# battery_box3.net
KiCad netlist of a schematic drawn in EAGLE
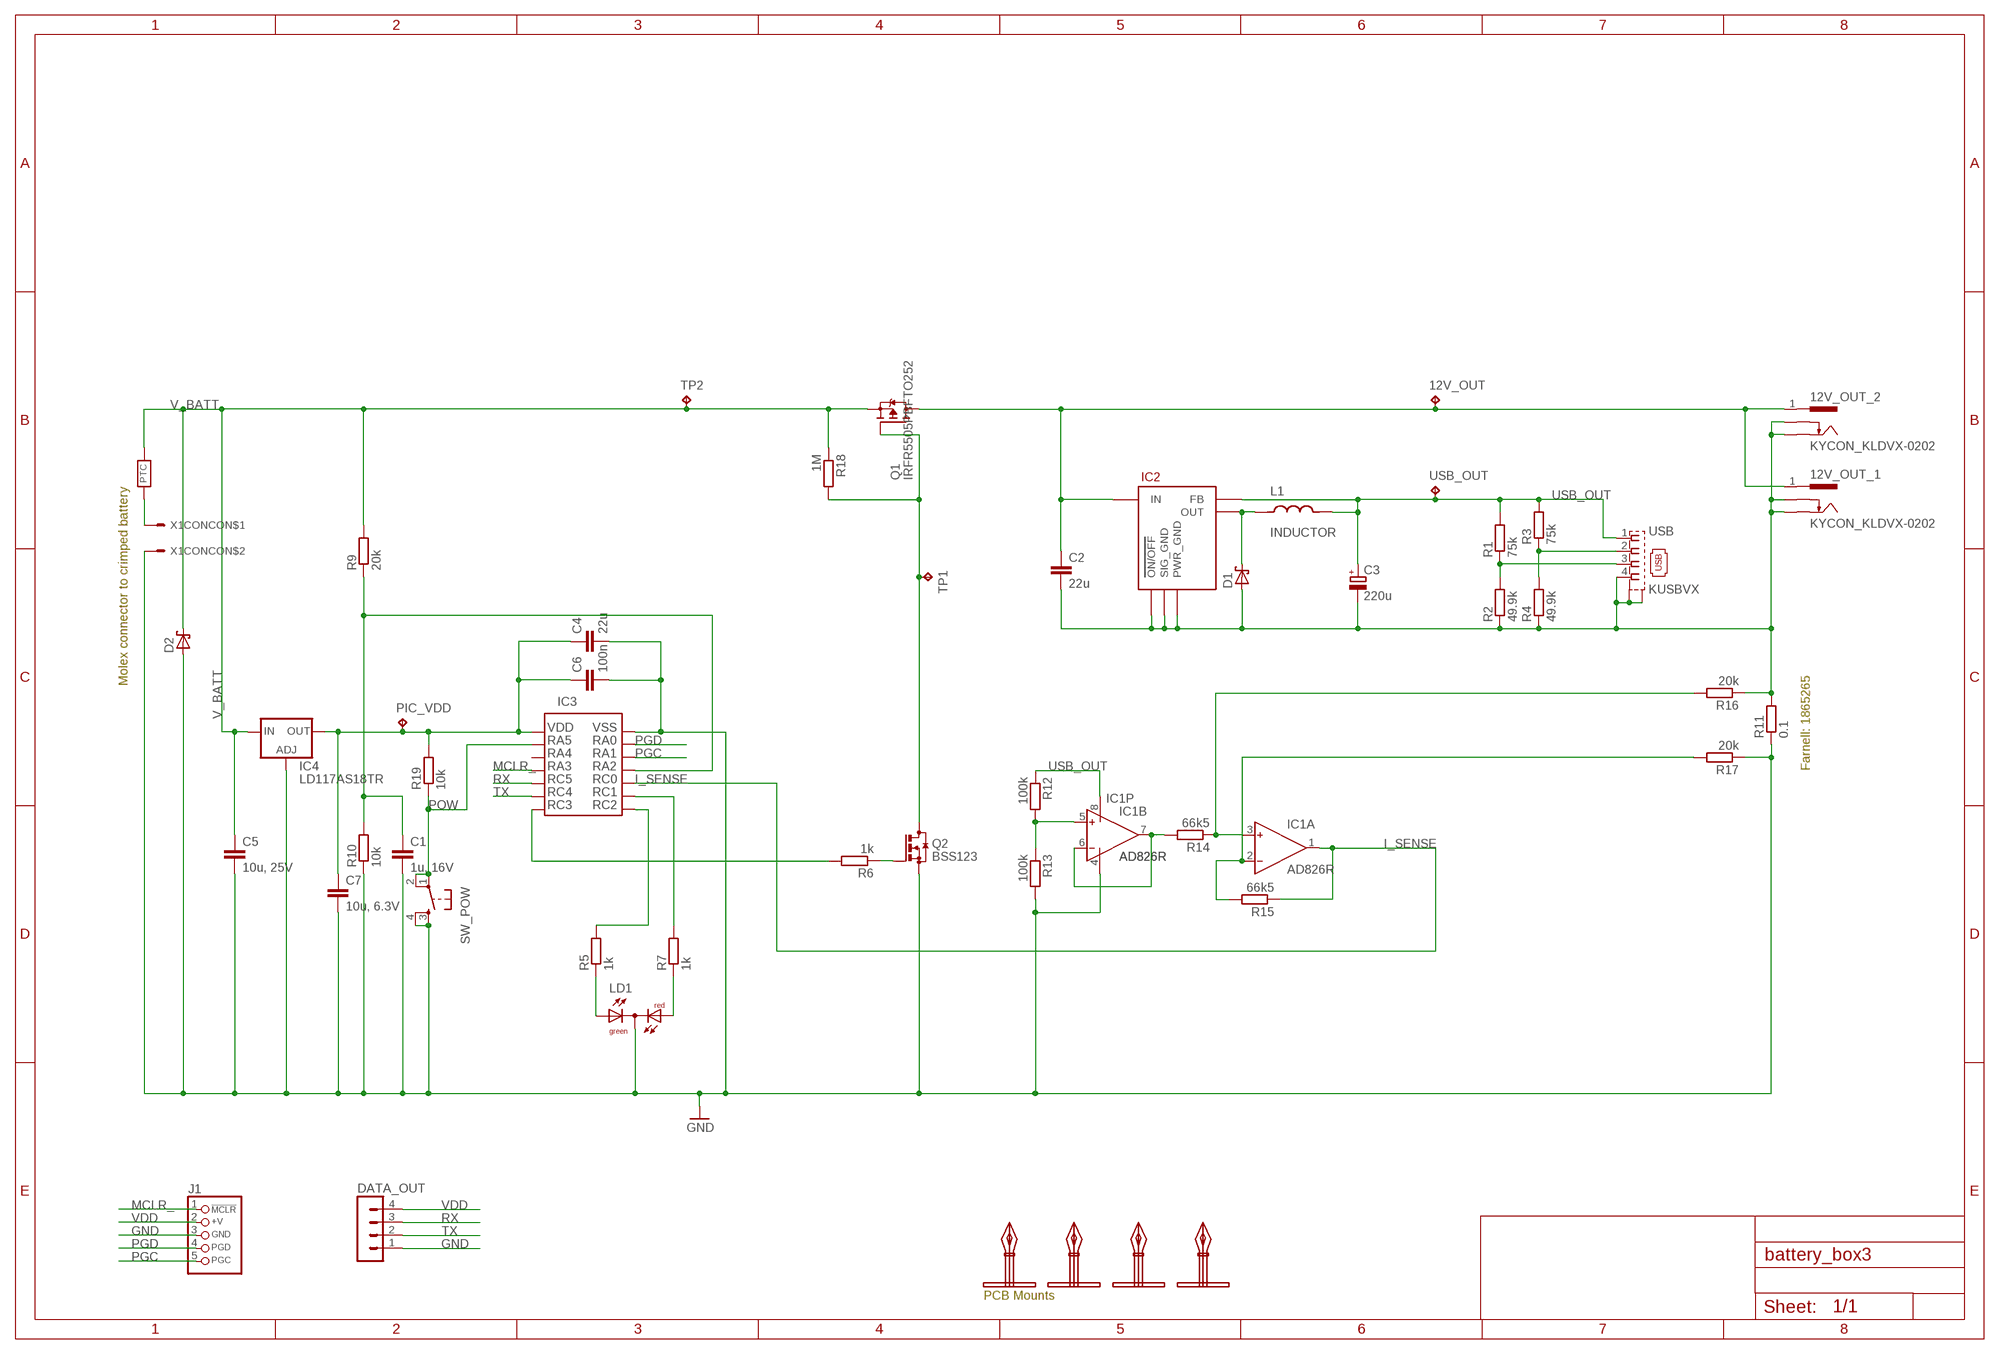
[diagram p0: schematic, sheet 1]

(export (version "E")
  (design (tool "Eeschema 10.0.6"))
  (components
    (comp (ref "12V_OUT")
      (value "TPTP20R")
      (footprint "eagle-import:TP20R")
      (libsource (lib "eagle-import") (part "TPTP20R"))
    )
    (comp (ref "12V_OUT_1")
      (value "KYCON_KLDVX-0202")
      (footprint "eagle-import:KYCON_KLVDX_2020_B")
      (libsource (lib "eagle-import") (part "KYCON_KLDVX-0202"))
    )
    (comp (ref "12V_OUT_2")
      (value "KYCON_KLDVX-0202")
      (footprint "eagle-import:KYCON_KLVDX_2020_B")
      (libsource (lib "eagle-import") (part "KYCON_KLDVX-0202"))
    )
    (comp (ref "C1")
      (value "1u, 16V")
      (footprint "eagle-import:C0805")
      (libsource (lib "eagle-import") (part "C-EUC0805"))
    )
    (comp (ref "C2")
      (value "22u")
      (footprint "eagle-import:C1210")
      (libsource (lib "eagle-import") (part "C-EUC1210"))
    )
    (comp (ref "C3")
      (value "220u")
      (footprint "eagle-import:PANASONIC_E")
      (libsource (lib "eagle-import") (part "CPOL-EUE"))
    )
    (comp (ref "C4")
      (value "22u")
      (footprint "eagle-import:C0805")
      (libsource (lib "eagle-import") (part "C-EUC0805"))
    )
    (comp (ref "C5")
      (value "10u, 25V")
      (footprint "eagle-import:C1210")
      (libsource (lib "eagle-import") (part "C-EUC1210"))
    )
    (comp (ref "C6")
      (value "100n")
      (footprint "eagle-import:C0402")
      (libsource (lib "eagle-import") (part "C-EUC0402"))
    )
    (comp (ref "C7")
      (value "10u, 6.3V")
      (footprint "eagle-import:C0805")
      (libsource (lib "eagle-import") (part "C-EUC0805"))
    )
    (comp (ref "D1")
      (value "SCHOTTKY-DIODESMD")
      (footprint "eagle-import:SMB")
      (libsource (lib "eagle-import") (part "SCHOTTKY-DIODESMD"))
    )
    (comp (ref "D2")
      (value "SCHOTTKY-DIODESMC")
      (footprint "eagle-import:SMC")
      (libsource (lib "eagle-import") (part "SCHOTTKY-DIODESMC"))
    )
    (comp (ref "DATA_OUT")
      (value "MA04-1")
      (footprint "eagle-import:MA04-1")
      (libsource (lib "eagle-import") (part "MA04-1"))
    )
    (comp (ref "IC1")
      (value "AD826R")
      (footprint "eagle-import:SO8")
      (libsource (lib "eagle-import") (part "AD826R"))
    )
    (comp (ref "IC2")
      (value "LM2574")
      (footprint "eagle-import:SO14W")
      (libsource (lib "eagle-import") (part "LM2574"))
    )
    (comp (ref "IC3")
      (value "PIC16F1824")
      (footprint "eagle-import:SO-14")
      (libsource (lib "eagle-import") (part "PIC16F1824"))
    )
    (comp (ref "IC4")
      (value "LD117AS18TR")
      (footprint "eagle-import:SOT223")
      (libsource (lib "eagle-import") (part "LD117A?S18TR"))
    )
    (comp (ref "J1")
      (value "CON_HEADER_PRG_PIC_ICSPA")
      (footprint "eagle-import:HEADER_PRG_1X05")
      (libsource (lib "eagle-import") (part "CON_HEADER_PRG_PIC_ICSPA"))
    )
    (comp (ref "L1")
      (value "INDUCTOR")
      (footprint "eagle-import:SMD_INDUCTOR")
      (libsource (lib "eagle-import") (part "INDUCTOR"))
    )
    (comp (ref "LD1")
      (value "DUOLED-RG-C")
      (footprint "eagle-import:DUOLED-C-5MM")
      (libsource (lib "eagle-import") (part "DUOLED-RG-C"))
    )
    (comp (ref "PIC_VDD")
      (value "TPTP14R")
      (footprint "eagle-import:TP14R")
      (libsource (lib "eagle-import") (part "TPTP14R"))
    )
    (comp (ref "Q1")
      (value "IRFR5505PBFTO252")
      (footprint "eagle-import:TO252")
      (libsource (lib "eagle-import") (part "IRFR5505PBFTO252"))
    )
    (comp (ref "Q2")
      (value "BSS123")
      (footprint "eagle-import:SOT23")
      (libsource (lib "eagle-import") (part "BSS123"))
    )
    (comp (ref "R1")
      (value "75k")
      (footprint "eagle-import:R0805")
      (libsource (lib "eagle-import") (part "R-EU_R0805"))
    )
    (comp (ref "R2")
      (value "49.9k")
      (footprint "eagle-import:R0805")
      (libsource (lib "eagle-import") (part "R-EU_R0805"))
    )
    (comp (ref "R3")
      (value "75k")
      (footprint "eagle-import:R0805")
      (libsource (lib "eagle-import") (part "R-EU_R0805"))
    )
    (comp (ref "R4")
      (value "49.9k")
      (footprint "eagle-import:R0805")
      (libsource (lib "eagle-import") (part "R-EU_R0805"))
    )
    (comp (ref "R5")
      (value "1k")
      (footprint "eagle-import:R0805")
      (libsource (lib "eagle-import") (part "R-EU_R0805"))
    )
    (comp (ref "R6")
      (value "1k")
      (footprint "eagle-import:R0805")
      (libsource (lib "eagle-import") (part "R-EU_R0805"))
    )
    (comp (ref "R7")
      (value "1k")
      (footprint "eagle-import:R0805")
      (libsource (lib "eagle-import") (part "R-EU_R0805"))
    )
    (comp (ref "R9")
      (value "20k")
      (footprint "eagle-import:R0805")
      (libsource (lib "eagle-import") (part "R-EU_R0805"))
    )
    (comp (ref "R10")
      (value "10k")
      (footprint "eagle-import:R0805")
      (libsource (lib "eagle-import") (part "R-EU_R0805"))
    )
    (comp (ref "R11")
      (value "0.1")
      (footprint "eagle-import:R2512")
      (libsource (lib "eagle-import") (part "R-EU_R2512"))
    )
    (comp (ref "R12")
      (value "100k")
      (footprint "eagle-import:R0805")
      (libsource (lib "eagle-import") (part "R-EU_R0805"))
    )
    (comp (ref "R13")
      (value "100k")
      (footprint "eagle-import:R0805")
      (libsource (lib "eagle-import") (part "R-EU_R0805"))
    )
    (comp (ref "R14")
      (value "66k5")
      (footprint "eagle-import:R0805")
      (libsource (lib "eagle-import") (part "R-EU_R0805"))
    )
    (comp (ref "R15")
      (value "66k5")
      (footprint "eagle-import:R0805")
      (libsource (lib "eagle-import") (part "R-EU_R0805"))
    )
    (comp (ref "R16")
      (value "20k")
      (footprint "eagle-import:R0805")
      (libsource (lib "eagle-import") (part "R-EU_R0805"))
    )
    (comp (ref "R17")
      (value "20k")
      (footprint "eagle-import:R0805")
      (libsource (lib "eagle-import") (part "R-EU_R0805"))
    )
    (comp (ref "R18")
      (value "1M")
      (footprint "eagle-import:R0805")
      (libsource (lib "eagle-import") (part "R-EU_R0805"))
    )
    (comp (ref "R19")
      (value "10k")
      (footprint "eagle-import:R0805")
      (libsource (lib "eagle-import") (part "R-EU_R0805"))
    )
    (comp (ref "SW_POW")
      (value "TAC_SWITCHPTH")
      (footprint "eagle-import:TACTILE-PTH")
      (libsource (lib "eagle-import") (part "TAC_SWITCHPTH"))
    )
    (comp (ref "TP1")
      (value "TPTP14R")
      (footprint "eagle-import:TP14R")
      (libsource (lib "eagle-import") (part "TPTP14R"))
    )
    (comp (ref "TP2")
      (value "TPTP20R")
      (footprint "eagle-import:TP20R")
      (libsource (lib "eagle-import") (part "TPTP20R"))
    )
    (comp (ref "U$2")
      (value "PTC")
      (footprint "eagle-import:MINISMDC260F")
      (libsource (lib "eagle-import") (part "PTC"))
    )
    (comp (ref "U$5")
      (value "PCB_MOUNT_RICHO")
      (footprint "eagle-import:PCBMOUNT")
      (libsource (lib "eagle-import") (part "PCB_MOUNT_RICHO"))
    )
    (comp (ref "U$6")
      (value "PCB_MOUNT_RICHO")
      (footprint "eagle-import:PCBMOUNT")
      (libsource (lib "eagle-import") (part "PCB_MOUNT_RICHO"))
    )
    (comp (ref "U$7")
      (value "PCB_MOUNT_RICHO")
      (footprint "eagle-import:PCBMOUNT")
      (libsource (lib "eagle-import") (part "PCB_MOUNT_RICHO"))
    )
    (comp (ref "U$8")
      (value "PCB_MOUNT_RICHO")
      (footprint "eagle-import:PCBMOUNT")
      (libsource (lib "eagle-import") (part "PCB_MOUNT_RICHO"))
    )
    (comp (ref "USB")
      (value "KUSBVX")
      (footprint "eagle-import:KUSBVX")
      (libsource (lib "eagle-import") (part "KUSBVX"))
    )
    (comp (ref "USB_OUT")
      (value "TPTP20R")
      (footprint "eagle-import:TP20R")
      (libsource (lib "eagle-import") (part "TPTP20R"))
    )
    (comp (ref "X1CON")
      (value "CON_MOLEX_39_29_1028")
      (footprint "eagle-import:MOLEX_39_29_1028")
      (libsource (lib "eagle-import") (part "CON_MOLEX_39_29_1028"))
    )
  )
  (nets
    (net (code "1") (name "/I_SENSE") (class "Default")
      (node (ref "IC1") (pin "1") (pinfunction "OUT_1") (pintype "output"))
      (node (ref "IC3") (pin "10") (pinfunction "P$10_10") (pintype "bidirectional"))
      (node (ref "R15") (pin "1") (pinfunction "1_1") (pintype "passive"))
    )
    (net (code "2") (name "/MCLR_") (class "Default")
      (node (ref "IC3") (pin "4") (pinfunction "P$4_4") (pintype "bidirectional"))
      (node (ref "J1") (pin "1") (pinfunction "/MCLR_1") (pintype "passive"))
    )
    (net (code "3") (name "/PGC") (class "Default")
      (node (ref "IC3") (pin "12") (pinfunction "P$12_12") (pintype "bidirectional"))
      (node (ref "J1") (pin "5") (pinfunction "PGC_5") (pintype "passive"))
    )
    (net (code "4") (name "/PGD") (class "Default")
      (node (ref "IC3") (pin "13") (pinfunction "P$13_13") (pintype "bidirectional"))
      (node (ref "J1") (pin "4") (pinfunction "PGD_4") (pintype "passive"))
    )
    (net (code "5") (name "/POW") (class "Default")
      (node (ref "IC3") (pin "2") (pinfunction "P$2_2") (pintype "bidirectional"))
      (node (ref "R19") (pin "1") (pinfunction "1_1") (pintype "passive"))
      (node (ref "SW_POW") (pin "1") (pinfunction "1_1") (pintype "passive"))
      (node (ref "SW_POW") (pin "2") (pinfunction "2_2") (pintype "passive"))
    )
    (net (code "6") (name "/RX") (class "Default")
      (node (ref "DATA_OUT") (pin "3") (pinfunction "3_3") (pintype "passive"))
      (node (ref "IC3") (pin "5") (pinfunction "P$5_5") (pintype "bidirectional"))
    )
    (net (code "7") (name "/TX") (class "Default")
      (node (ref "DATA_OUT") (pin "2") (pinfunction "2_2") (pintype "passive"))
      (node (ref "IC3") (pin "6") (pinfunction "P$6_6") (pintype "bidirectional"))
    )
    (net (code "8") (name "/USB_OUT") (class "Default")
      (node (ref "C3") (pin "+") (pinfunction "+_+") (pintype "passive"))
      (node (ref "IC1") (pin "8") (pinfunction "V+_8") (pintype "power_in"))
      (node (ref "IC2") (pin "3") (pinfunction "FB_3") (pintype "bidirectional"))
      (node (ref "L1") (pin "P$2") (pinfunction "P$2_P$2") (pintype "bidirectional"))
      (node (ref "R1") (pin "2") (pinfunction "2_2") (pintype "passive"))
      (node (ref "R12") (pin "1") (pinfunction "1_1") (pintype "passive"))
      (node (ref "R3") (pin "2") (pinfunction "2_2") (pintype "passive"))
      (node (ref "USB") (pin "1") (pinfunction "1_1") (pintype "passive"))
      (node (ref "USB_OUT") (pin "TP") (pinfunction "TP_TP") (pintype "input"))
    )
    (net (code "9") (name "/VDD") (class "Default")
      (node (ref "C4") (pin "1") (pinfunction "1_1") (pintype "passive"))
      (node (ref "C6") (pin "1") (pinfunction "1_1") (pintype "passive"))
      (node (ref "C7") (pin "1") (pinfunction "1_1") (pintype "passive"))
      (node (ref "DATA_OUT") (pin "4") (pinfunction "4_4") (pintype "passive"))
      (node (ref "IC3") (pin "1") (pinfunction "P$1_1") (pintype "bidirectional"))
      (node (ref "IC4") (pin "4") (pinfunction "OUT_4") (pintype "passive"))
      (node (ref "J1") (pin "2") (pinfunction "+V_2") (pintype "passive"))
      (node (ref "PIC_VDD") (pin "TP") (pinfunction "TP_TP") (pintype "input"))
      (node (ref "R19") (pin "2") (pinfunction "2_2") (pintype "passive"))
    )
    (net (code "10") (name "/V_BATT") (class "Default")
      (node (ref "C5") (pin "1") (pinfunction "1_1") (pintype "passive"))
      (node (ref "D2") (pin "C") (pinfunction "C_C") (pintype "passive"))
      (node (ref "IC4") (pin "3") (pinfunction "IN_3") (pintype "input"))
      (node (ref "Q1") (pin "2") (pinfunction "S_2") (pintype "passive"))
      (node (ref "R18") (pin "1") (pinfunction "1_1") (pintype "passive"))
      (node (ref "R9") (pin "2") (pinfunction "2_2") (pintype "passive"))
      (node (ref "TP2") (pin "TP") (pinfunction "TP_TP") (pintype "input"))
      (node (ref "U$2") (pin "P$2") (pinfunction "P$2_P$2") (pintype "bidirectional"))
    )
    (net (code "11") (name "GND") (class "Default")
      (node (ref "C1") (pin "2") (pinfunction "2_2") (pintype "passive"))
      (node (ref "C4") (pin "2") (pinfunction "2_2") (pintype "passive"))
      (node (ref "C5") (pin "2") (pinfunction "2_2") (pintype "passive"))
      (node (ref "C6") (pin "2") (pinfunction "2_2") (pintype "passive"))
      (node (ref "C7") (pin "2") (pinfunction "2_2") (pintype "passive"))
      (node (ref "D2") (pin "A") (pinfunction "A_A") (pintype "passive"))
      (node (ref "DATA_OUT") (pin "1") (pinfunction "1_1") (pintype "passive"))
      (node (ref "IC1") (pin "4") (pinfunction "V-_4") (pintype "power_in"))
      (node (ref "IC3") (pin "14") (pinfunction "P$14_14") (pintype "bidirectional"))
      (node (ref "IC4") (pin "1") (pinfunction "ADJ_1") (pintype "input"))
      (node (ref "J1") (pin "3") (pinfunction "GND_3") (pintype "passive"))
      (node (ref "LD1") (pin "C") (pinfunction "C_C") (pintype "passive"))
      (node (ref "Q2") (pin "2") (pinfunction "S_2") (pintype "passive"))
      (node (ref "R10") (pin "1") (pinfunction "1_1") (pintype "passive"))
      (node (ref "R11") (pin "1") (pinfunction "1_1") (pintype "passive"))
      (node (ref "R13") (pin "2") (pinfunction "2_2") (pintype "passive"))
      (node (ref "R17") (pin "1") (pinfunction "1_1") (pintype "passive"))
      (node (ref "SW_POW") (pin "3") (pinfunction "3_3") (pintype "passive"))
      (node (ref "SW_POW") (pin "4") (pinfunction "4_4") (pintype "passive"))
      (node (ref "X1CON") (pin "P$2") (pinfunction "S_P$2") (pintype "passive"))
    )
    (net (code "12") (name "Net-(12V_OUT_1-PAD1)") (class "Default")
      (node (ref "12V_OUT") (pin "TP") (pinfunction "TP_TP") (pintype "input"))
      (node (ref "12V_OUT_1") (pin "1") (pinfunction "PAD1_1") (pintype "passive"))
      (node (ref "12V_OUT_2") (pin "1") (pinfunction "PAD1_1") (pintype "passive"))
      (node (ref "C2") (pin "1") (pinfunction "1_1") (pintype "passive"))
      (node (ref "IC2") (pin "10") (pinfunction "IN_10") (pintype "bidirectional"))
      (node (ref "Q1") (pin "3") (pinfunction "D_3") (pintype "passive"))
    )
    (net (code "13") (name "Net-(12V_OUT_1-PAD2)") (class "Default")
      (node (ref "12V_OUT_1") (pin "2") (pinfunction "PAD2_2") (pintype "passive"))
      (node (ref "12V_OUT_1") (pin "3") (pinfunction "PAD3_3") (pintype "passive"))
      (node (ref "12V_OUT_2") (pin "2") (pinfunction "PAD2_2") (pintype "passive"))
      (node (ref "12V_OUT_2") (pin "3") (pinfunction "PAD3_3") (pintype "passive"))
      (node (ref "C2") (pin "2") (pinfunction "2_2") (pintype "passive"))
      (node (ref "C3") (pin "-") (pinfunction "-_-") (pintype "passive"))
      (node (ref "D1") (pin "A") (pinfunction "A_A") (pintype "passive"))
      (node (ref "IC2") (pin "4") (pinfunction "SIG_GND_4") (pintype "bidirectional"))
      (node (ref "IC2") (pin "5") (pinfunction "ON/OFF_5") (pintype "bidirectional"))
      (node (ref "IC2") (pin "6") (pinfunction "PWR_GND_6") (pintype "bidirectional"))
      (node (ref "R11") (pin "2") (pinfunction "2_2") (pintype "passive"))
      (node (ref "R16") (pin "1") (pinfunction "1_1") (pintype "passive"))
      (node (ref "R2") (pin "1") (pinfunction "1_1") (pintype "passive"))
      (node (ref "R4") (pin "1") (pinfunction "1_1") (pintype "passive"))
      (node (ref "USB") (pin "4") (pinfunction "4_4") (pintype "passive"))
      (node (ref "USB") (pin "M1") (pinfunction "S1_M1") (pintype "passive"))
      (node (ref "USB") (pin "M2") (pinfunction "S2_M2") (pintype "passive"))
    )
    (net (code "14") (name "Net-(IC1A-IN+)") (class "Default")
      (node (ref "IC1") (pin "3") (pinfunction "IN+_3") (pintype "input"))
      (node (ref "R14") (pin "1") (pinfunction "1_1") (pintype "passive"))
      (node (ref "R16") (pin "2") (pinfunction "2_2") (pintype "passive"))
    )
    (net (code "15") (name "Net-(IC1A-IN-)") (class "Default")
      (node (ref "IC1") (pin "2") (pinfunction "IN-_2") (pintype "input"))
      (node (ref "R15") (pin "2") (pinfunction "2_2") (pintype "passive"))
      (node (ref "R17") (pin "2") (pinfunction "2_2") (pintype "passive"))
    )
    (net (code "16") (name "Net-(IC1B-IN+)") (class "Default")
      (node (ref "IC1") (pin "5") (pinfunction "IN+_5") (pintype "input"))
      (node (ref "R12") (pin "2") (pinfunction "2_2") (pintype "passive"))
      (node (ref "R13") (pin "1") (pinfunction "1_1") (pintype "passive"))
    )
    (net (code "17") (name "Net-(IC1B-IN-)") (class "Default")
      (node (ref "IC1") (pin "6") (pinfunction "IN-_6") (pintype "input"))
      (node (ref "IC1") (pin "7") (pinfunction "OUT_7") (pintype "output"))
      (node (ref "R14") (pin "2") (pinfunction "2_2") (pintype "passive"))
    )
    (net (code "18") (name "Net-(IC2-OUT)") (class "Default")
      (node (ref "D1") (pin "C") (pinfunction "C_C") (pintype "passive"))
      (node (ref "IC2") (pin "12") (pinfunction "OUT_12") (pintype "bidirectional"))
      (node (ref "L1") (pin "P$1") (pinfunction "P$1_P$1") (pintype "bidirectional"))
    )
    (net (code "19") (name "Net-(IC3-P$7)") (class "Default")
      (node (ref "IC3") (pin "7") (pinfunction "P$7_7") (pintype "bidirectional"))
      (node (ref "R6") (pin "2") (pinfunction "2_2") (pintype "passive"))
    )
    (net (code "20") (name "Net-(IC3-P$8)") (class "Default")
      (node (ref "IC3") (pin "8") (pinfunction "P$8_8") (pintype "bidirectional"))
      (node (ref "R5") (pin "2") (pinfunction "2_2") (pintype "passive"))
    )
    (net (code "21") (name "Net-(IC3-P$9)") (class "Default")
      (node (ref "IC3") (pin "9") (pinfunction "P$9_9") (pintype "bidirectional"))
      (node (ref "R7") (pin "2") (pinfunction "2_2") (pintype "passive"))
    )
    (net (code "22") (name "Net-(IC3-P$11)") (class "Default")
      (node (ref "C1") (pin "1") (pinfunction "1_1") (pintype "passive"))
      (node (ref "IC3") (pin "11") (pinfunction "P$11_11") (pintype "bidirectional"))
      (node (ref "R10") (pin "2") (pinfunction "2_2") (pintype "passive"))
      (node (ref "R9") (pin "1") (pinfunction "1_1") (pintype "passive"))
    )
    (net (code "23") (name "Net-(LD1-AG)") (class "Default")
      (node (ref "LD1") (pin "AX") (pinfunction "AG_AX") (pintype "passive"))
      (node (ref "R5") (pin "1") (pinfunction "1_1") (pintype "passive"))
    )
    (net (code "24") (name "Net-(LD1-PadAR)") (class "Default")
      (node (ref "LD1") (pin "AR") (pinfunction "AR_AR") (pintype "passive"))
      (node (ref "R7") (pin "1") (pinfunction "1_1") (pintype "passive"))
    )
    (net (code "25") (name "Net-(Q1-G)") (class "Default")
      (node (ref "Q1") (pin "1") (pinfunction "G_1") (pintype "passive"))
      (node (ref "Q2") (pin "3") (pinfunction "D_3") (pintype "passive"))
      (node (ref "R18") (pin "2") (pinfunction "2_2") (pintype "passive"))
      (node (ref "TP1") (pin "TP") (pinfunction "TP_TP") (pintype "input"))
    )
    (net (code "26") (name "Net-(Q2-G)") (class "Default")
      (node (ref "Q2") (pin "1") (pinfunction "G_1") (pintype "passive"))
      (node (ref "R6") (pin "1") (pinfunction "1_1") (pintype "passive"))
    )
    (net (code "27") (name "Net-(R1-Pad1)") (class "Default")
      (node (ref "R1") (pin "1") (pinfunction "1_1") (pintype "passive"))
      (node (ref "R2") (pin "2") (pinfunction "2_2") (pintype "passive"))
      (node (ref "USB") (pin "3") (pinfunction "3_3") (pintype "passive"))
    )
    (net (code "28") (name "Net-(R3-Pad1)") (class "Default")
      (node (ref "R3") (pin "1") (pinfunction "1_1") (pintype "passive"))
      (node (ref "R4") (pin "2") (pinfunction "2_2") (pintype "passive"))
      (node (ref "USB") (pin "2") (pinfunction "2_2") (pintype "passive"))
    )
    (net (code "29") (name "Net-(X1CONA-S)") (class "Default")
      (node (ref "U$2") (pin "P$1") (pinfunction "P$1_P$1") (pintype "bidirectional"))
      (node (ref "X1CON") (pin "P$1") (pinfunction "S_P$1") (pintype "passive"))
    )
    (net (code "30") (name "unconnected-(IC3-P$3-Pad3)") (class "Default")
      (node (ref "IC3") (pin "3") (pinfunction "P$3_3") (pintype "bidirectional"))
    )
  )
)
